# untitled.net
KiCad netlist of a schematic drawn in EAGLE
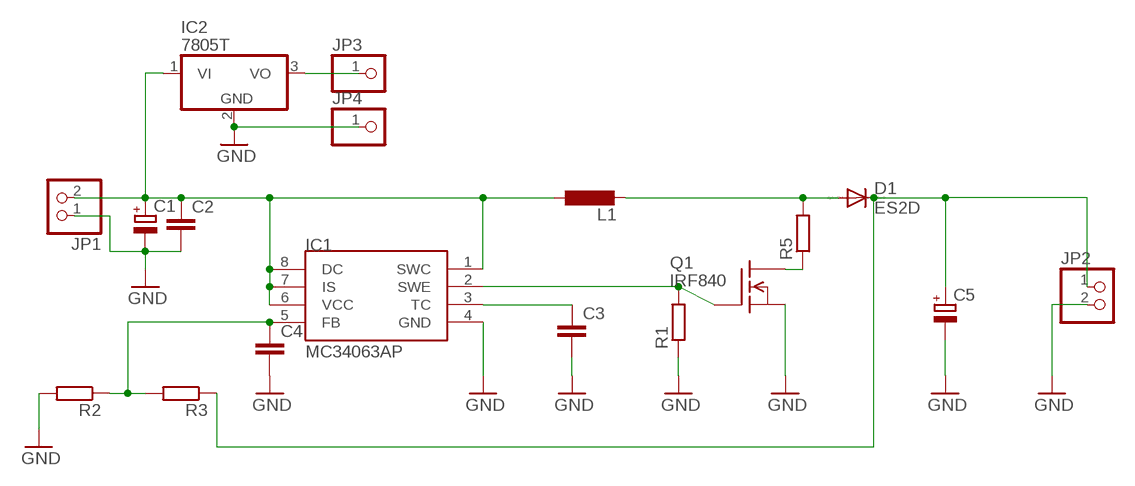
[diagram p0: schematic, sheet 1]

(export (version "E")
  (design (tool "Eeschema 10.0.6"))
  (components
    (comp (ref "C1")
      (value "CPOL-EUE3.5-8")
      (footprint "eagle-import:E3,5-8")
      (libsource (lib "eagle-import") (part "CPOL-EUE3.5-8"))
    )
    (comp (ref "C2")
      (value "C-EU050-025X075")
      (footprint "eagle-import:C050-025X075")
      (libsource (lib "eagle-import") (part "C-EU050-025X075"))
    )
    (comp (ref "C3")
      (value "C-EU050-025X075")
      (footprint "eagle-import:C050-025X075")
      (libsource (lib "eagle-import") (part "C-EU050-025X075"))
    )
    (comp (ref "C4")
      (value "C-EU050-025X075")
      (footprint "eagle-import:C050-025X075")
      (libsource (lib "eagle-import") (part "C-EU050-025X075"))
    )
    (comp (ref "C5")
      (value "CPOL-EUE3.5-8")
      (footprint "eagle-import:E3,5-8")
      (libsource (lib "eagle-import") (part "CPOL-EUE3.5-8"))
    )
    (comp (ref "D1")
      (value "ES2D")
      (footprint "eagle-import:SMB")
      (libsource (lib "eagle-import") (part "ES2D"))
    )
    (comp (ref "IC1")
      (value "MC34063AP")
      (footprint "eagle-import:DIL08")
      (libsource (lib "eagle-import") (part "MC34063AP"))
    )
    (comp (ref "IC2")
      (value "7805T")
      (footprint "eagle-import:TO220H")
      (libsource (lib "eagle-import") (part "78T05"))
    )
    (comp (ref "JP1")
      (value "PINHD-1X2")
      (footprint "eagle-import:1X02")
      (libsource (lib "eagle-import") (part "PINHD-1X2"))
    )
    (comp (ref "JP2")
      (value "PINHD-1X2")
      (footprint "eagle-import:1X02")
      (libsource (lib "eagle-import") (part "PINHD-1X2"))
    )
    (comp (ref "JP3")
      (value "PINHD-1X1")
      (footprint "eagle-import:1X01")
      (libsource (lib "eagle-import") (part "PINHD-1X1"))
    )
    (comp (ref "JP4")
      (value "PINHD-1X1")
      (footprint "eagle-import:1X01")
      (libsource (lib "eagle-import") (part "PINHD-1X1"))
    )
    (comp (ref "L1")
      (value "L-EUTJ3-U1")
      (footprint "eagle-import:TJ3-U1")
      (libsource (lib "eagle-import") (part "L-EUTJ3-U1"))
    )
    (comp (ref "Q1")
      (value "IRF840")
      (footprint "eagle-import:TO220")
      (libsource (lib "eagle-import") (part "IRF840"))
    )
    (comp (ref "R1")
      (value "R-EU_0207/7")
      (footprint "eagle-import:0207_7")
      (libsource (lib "eagle-import") (part "R-EU_0207/7"))
    )
    (comp (ref "R2")
      (value "R-EU_0207/7")
      (footprint "eagle-import:0207_7")
      (libsource (lib "eagle-import") (part "R-EU_0207/7"))
    )
    (comp (ref "R3")
      (value "R-EU_0207/7")
      (footprint "eagle-import:0207_7")
      (libsource (lib "eagle-import") (part "R-EU_0207/7"))
    )
    (comp (ref "R5")
      (value "R-EU_0207/15")
      (footprint "eagle-import:0207_15")
      (libsource (lib "eagle-import") (part "R-EU_0207/15"))
    )
  )
  (nets
    (net (code "1") (name "GND") (class "Default")
      (node (ref "C1") (pin "-") (pinfunction "-_-") (pintype "passive"))
      (node (ref "C2") (pin "2") (pinfunction "2_2") (pintype "passive"))
      (node (ref "C3") (pin "2") (pinfunction "2_2") (pintype "passive"))
      (node (ref "C4") (pin "2") (pinfunction "2_2") (pintype "passive"))
      (node (ref "C5") (pin "-") (pinfunction "-_-") (pintype "passive"))
      (node (ref "IC1") (pin "4") (pinfunction "GND_4") (pintype "passive"))
      (node (ref "IC2") (pin "2") (pinfunction "GND_2") (pintype "passive"))
      (node (ref "JP1") (pin "1") (pinfunction "1_1") (pintype "passive"))
      (node (ref "JP2") (pin "2") (pinfunction "2_2") (pintype "passive"))
      (node (ref "JP4") (pin "1") (pinfunction "1_1") (pintype "passive"))
      (node (ref "Q1") (pin "3") (pinfunction "S_3") (pintype "passive"))
      (node (ref "R1") (pin "1") (pinfunction "1_1") (pintype "passive"))
      (node (ref "R2") (pin "2") (pinfunction "2_2") (pintype "passive"))
    )
    (net (code "2") (name "Net-(C5-Pad+)") (class "Default")
      (node (ref "C5") (pin "+") (pinfunction "+_+") (pintype "passive"))
      (node (ref "D1") (pin "C") (pinfunction "C_C") (pintype "passive"))
      (node (ref "JP2") (pin "1") (pinfunction "1_1") (pintype "passive"))
      (node (ref "R3") (pin "1") (pinfunction "1_1") (pintype "passive"))
    )
    (net (code "3") (name "Net-(D1-PadA)") (class "Default")
      (node (ref "D1") (pin "A") (pinfunction "A_A") (pintype "passive"))
      (node (ref "L1") (pin "2") (pinfunction "2_2") (pintype "passive"))
      (node (ref "R5") (pin "2") (pinfunction "2_2") (pintype "passive"))
    )
    (net (code "4") (name "Net-(IC1-DC)") (class "Default")
      (node (ref "C1") (pin "+") (pinfunction "+_+") (pintype "passive"))
      (node (ref "C2") (pin "1") (pinfunction "1_1") (pintype "passive"))
      (node (ref "IC1") (pin "1") (pinfunction "SWC_1") (pintype "passive"))
      (node (ref "IC1") (pin "6") (pinfunction "VCC_6") (pintype "passive"))
      (node (ref "IC1") (pin "7") (pinfunction "IS_7") (pintype "passive"))
      (node (ref "IC1") (pin "8") (pinfunction "DC_8") (pintype "passive"))
      (node (ref "IC2") (pin "1") (pinfunction "VI_1") (pintype "input"))
      (node (ref "JP1") (pin "2") (pinfunction "2_2") (pintype "passive"))
      (node (ref "L1") (pin "1") (pinfunction "1_1") (pintype "passive"))
    )
    (net (code "5") (name "Net-(IC1-FB)") (class "Default")
      (node (ref "C4") (pin "1") (pinfunction "1_1") (pintype "passive"))
      (node (ref "IC1") (pin "5") (pinfunction "FB_5") (pintype "passive"))
      (node (ref "R2") (pin "1") (pinfunction "1_1") (pintype "passive"))
      (node (ref "R3") (pin "2") (pinfunction "2_2") (pintype "passive"))
    )
    (net (code "6") (name "Net-(IC1-SWE)") (class "Default")
      (node (ref "IC1") (pin "2") (pinfunction "SWE_2") (pintype "passive"))
      (node (ref "Q1") (pin "1") (pinfunction "G_1") (pintype "passive"))
      (node (ref "R1") (pin "2") (pinfunction "2_2") (pintype "passive"))
    )
    (net (code "7") (name "Net-(IC1-TC)") (class "Default")
      (node (ref "C3") (pin "1") (pinfunction "1_1") (pintype "passive"))
      (node (ref "IC1") (pin "3") (pinfunction "TC_3") (pintype "passive"))
    )
    (net (code "8") (name "Net-(IC2-VO)") (class "Default")
      (node (ref "IC2") (pin "3") (pinfunction "VO_3") (pintype "passive"))
      (node (ref "JP3") (pin "1") (pinfunction "1_1") (pintype "passive"))
    )
    (net (code "9") (name "Net-(Q1-D)") (class "Default")
      (node (ref "Q1") (pin "2") (pinfunction "D_2") (pintype "passive"))
      (node (ref "R5") (pin "1") (pinfunction "1_1") (pintype "passive"))
    )
  )
)
